# LED.net
KiCad netlist of a schematic drawn in Altium Designer
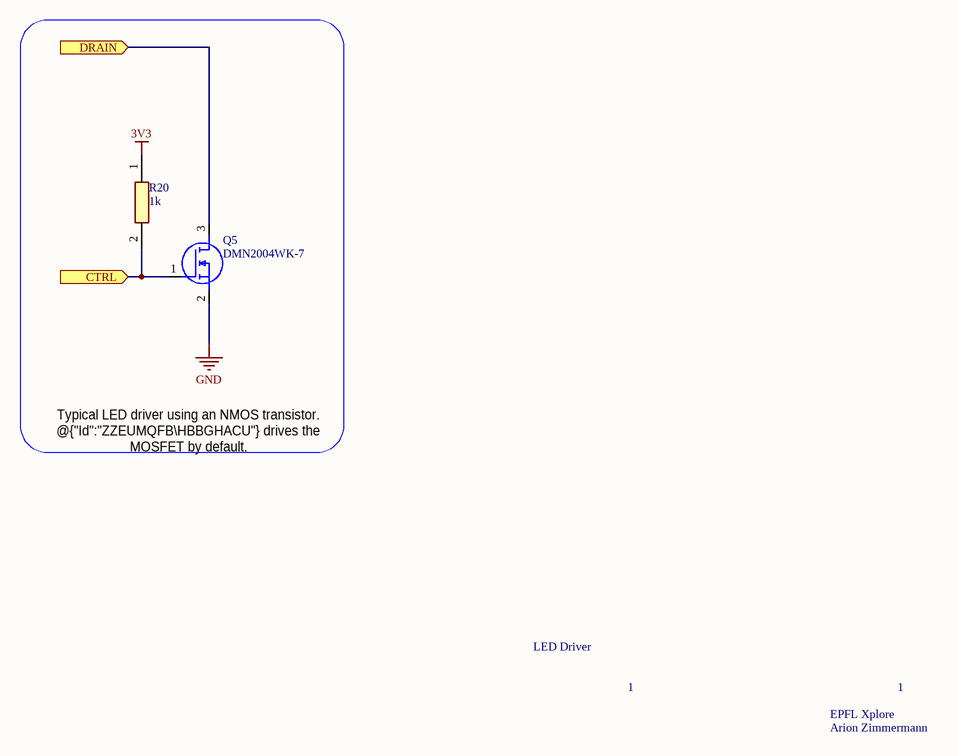
[diagram p0: LED.SchDoc]

(export (version "E")
  (design (tool "Eeschema 10.0.6"))
  (components
    (comp (ref "Q5")
      (value "DMN2004WK-7")
      (footprint "SamacSys:SOT65P210X110-3N")
      (description "MOSFET (N-Channel)")
      (fields (field (name "MOUSER PART NUMBER") "621-DMN2004WK-7"))
      (libsource (lib "SamacSys") (part "DMN2004WK-7"))
    )
    (comp (ref "R20")
      (value "1k")
      (footprint "SamacSys:RESC1608X55N")
      (description "Resistor")
      (fields
        (field (name "MANUFACTURER_PART_NUMBER") "CRCW06031K00JNEAC")
        (field (name "MOUSER PART NUMBER") "71-CRCW06031K00JNEAC")
      )
      (libsource (lib "CarrierBoard") (part "CRCW06031K00JNEAC"))
    )
  )
  (nets
    (net (code "1") (name "/CTRL") (class "Default")
      (node (ref "Q5") (pin "1") (pinfunction "G_1") (pintype "passive"))
      (node (ref "R20") (pin "2") (pinfunction "2_2") (pintype "passive"))
    )
    (net (code "2") (name "/DRAIN") (class "Default")
      (node (ref "Q5") (pin "3") (pinfunction "D_3") (pintype "passive"))
    )
    (net (code "3") (name "3V3") (class "Default")
      (node (ref "R20") (pin "1") (pinfunction "1_1") (pintype "passive"))
    )
    (net (code "4") (name "GND") (class "Default")
      (node (ref "Q5") (pin "2") (pinfunction "S_2") (pintype "passive"))
    )
  )
)
